# clvHd_EMG.net
KiCad netlist of a schematic drawn in EAGLE
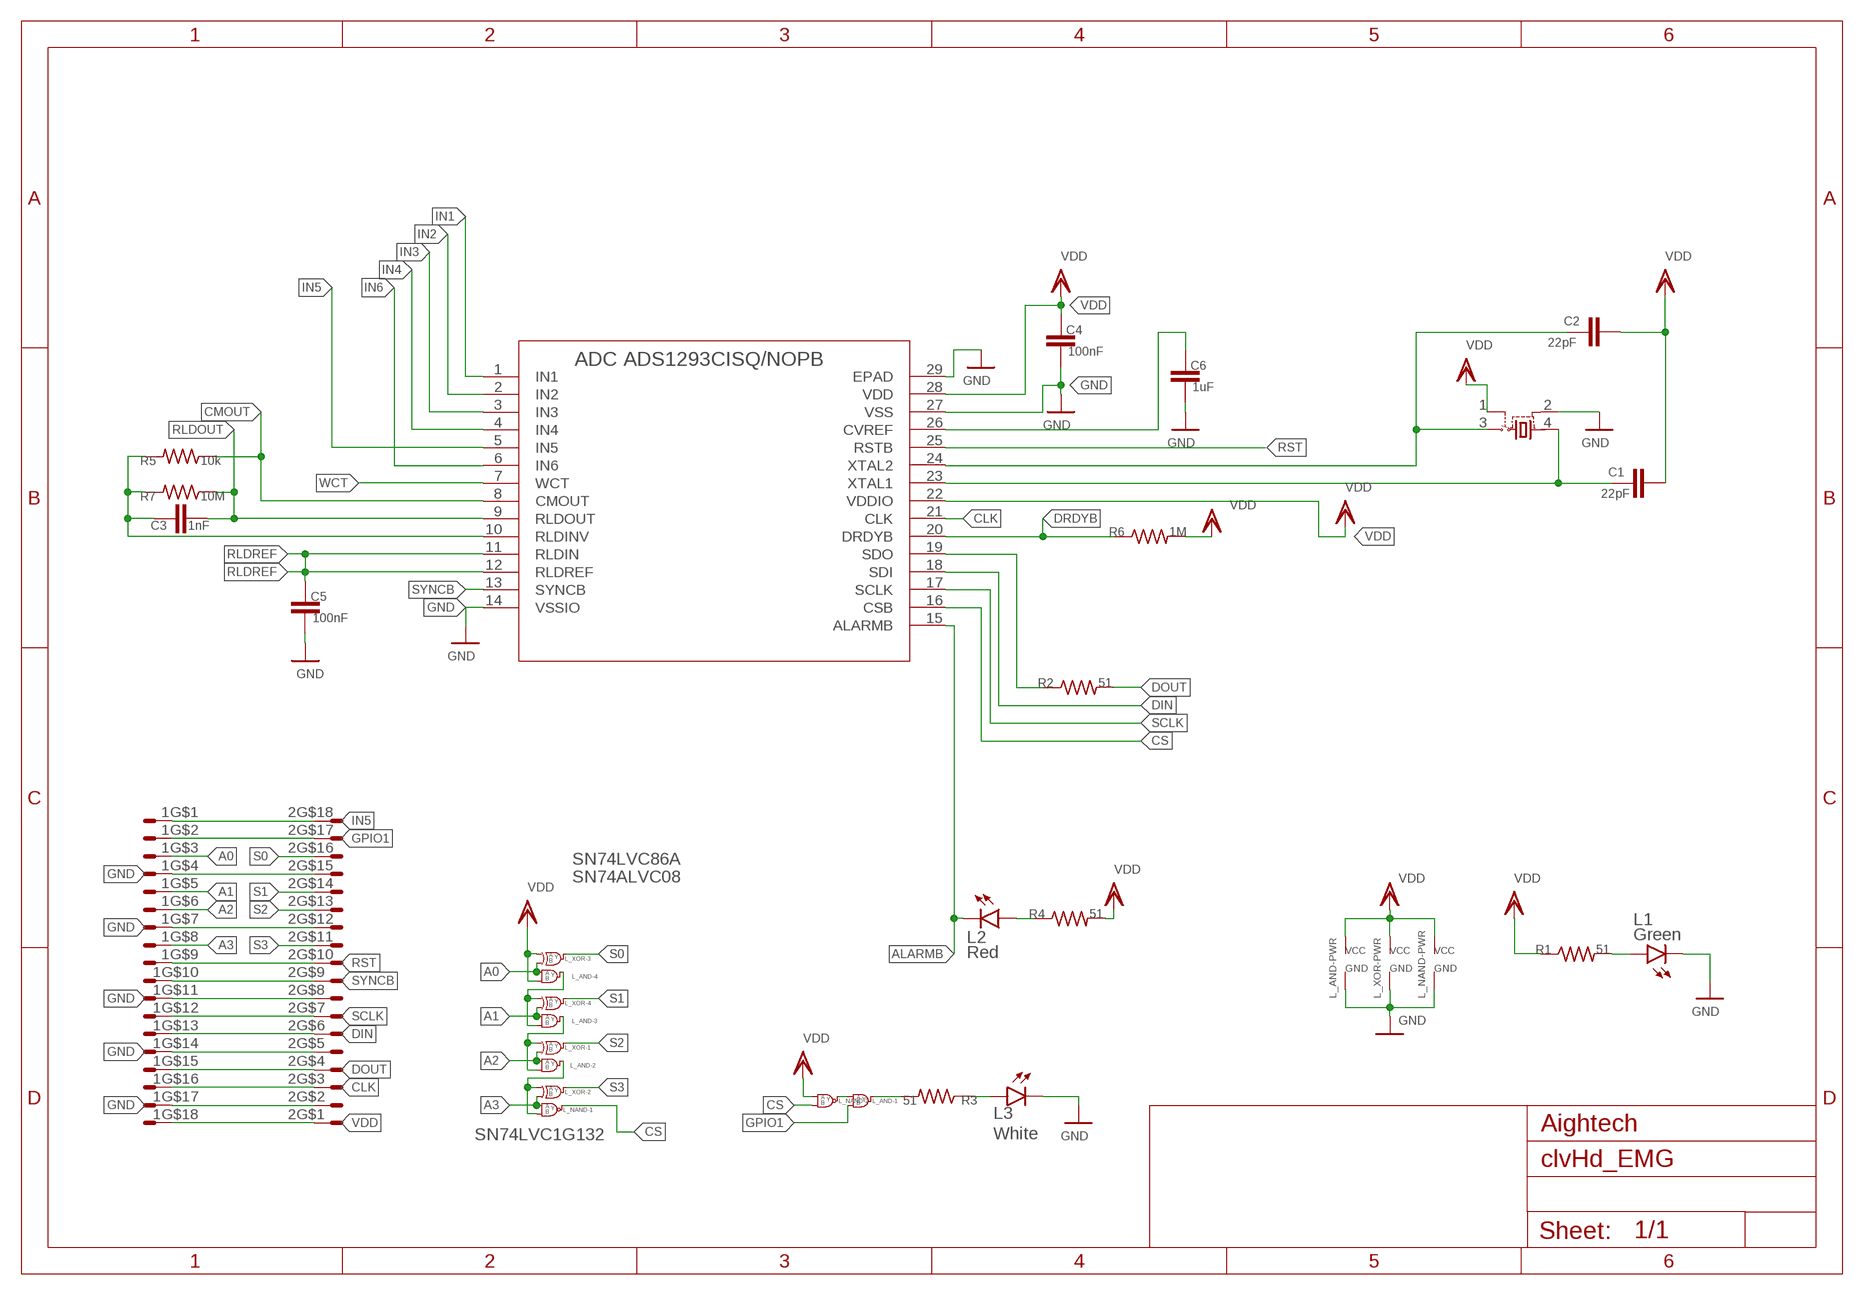
[diagram p0: schematic, sheet 1]

(export (version "E")
  (design (tool "Eeschema 10.0.6"))
  (components
    (comp (ref "1")
      (value "X05C2018TZ")
      (footprint "eagle-import:X05C2018TZ")
      (libsource (lib "eagle-import") (part "X05C2018TZ"))
    )
    (comp (ref "2")
      (value "X05C2018TZ")
      (footprint "eagle-import:X05C2018TZ")
      (libsource (lib "eagle-import") (part "X05C2018TZ"))
    )
    (comp (ref "ADC")
      (value "ADS1293CISQ/NOPB")
      (footprint "eagle-import:RSG28_3P6X3P6_TEX")
      (libsource (lib "eagle-import") (part "ADS1293CISQ/NOPB"))
    )
    (comp (ref "C1")
      (value "22pF")
      (footprint "eagle-import:C0402")
      (libsource (lib "eagle-import") (part "C-EUC0402"))
    )
    (comp (ref "C2")
      (value "22pF")
      (footprint "eagle-import:C0402")
      (libsource (lib "eagle-import") (part "C-EUC0402"))
    )
    (comp (ref "C3")
      (value "1nF")
      (footprint "eagle-import:C0402")
      (libsource (lib "eagle-import") (part "C-EUC0402"))
    )
    (comp (ref "C4")
      (value "100nF")
      (footprint "eagle-import:C0402")
      (libsource (lib "eagle-import") (part "C-EUC0402"))
    )
    (comp (ref "C5")
      (value "100nF")
      (footprint "eagle-import:C0402")
      (libsource (lib "eagle-import") (part "C-EUC0402"))
    )
    (comp (ref "C6")
      (value "1uF")
      (footprint "eagle-import:C0402")
      (libsource (lib "eagle-import") (part "C-EUC0402"))
    )
    (comp (ref "L1")
      (value "Green")
      (footprint "eagle-import:CHIP-LED0603")
      (libsource (lib "eagle-import") (part "LEDCHIP-LED0603"))
    )
    (comp (ref "L2")
      (value "Red")
      (footprint "eagle-import:CHIP-LED0603")
      (libsource (lib "eagle-import") (part "LEDCHIP-LED0603"))
    )
    (comp (ref "L3")
      (value "White")
      (footprint "eagle-import:CHIP-LED0603")
      (libsource (lib "eagle-import") (part "LEDCHIP-LED0603"))
    )
    (comp (ref "L_AND")
      (value "SN74ALVC08")
      (footprint "eagle-import:VQFN-14-CUSTOM")
      (libsource (lib "eagle-import") (part "SN74ALVC08RGY-LARGE"))
    )
    (comp (ref "L_NAND")
      (value "SN74AUP2G00")
      (footprint "eagle-import:VSSOP")
      (libsource (lib "eagle-import") (part "SN74AUP2G00DCU"))
    )
    (comp (ref "L_XOR")
      (value "SN74LVC86")
      (footprint "eagle-import:VQFN-14-CUSTOM")
      (libsource (lib "eagle-import") (part "SN74LVC86ARGY-LARGE"))
    )
    (comp (ref "R1")
      (value "51")
      (footprint "eagle-import:R0402")
      (libsource (lib "eagle-import") (part "rcl_334_R-US_R0402"))
    )
    (comp (ref "R2")
      (value "51")
      (footprint "eagle-import:R0402")
      (libsource (lib "eagle-import") (part "rcl_334_R-US_R0402"))
    )
    (comp (ref "R3")
      (value "51")
      (footprint "eagle-import:R0402")
      (libsource (lib "eagle-import") (part "rcl_334_R-US_R0402"))
    )
    (comp (ref "R4")
      (value "51")
      (footprint "eagle-import:R0402")
      (libsource (lib "eagle-import") (part "rcl_334_R-US_R0402"))
    )
    (comp (ref "R5")
      (value "10k")
      (footprint "eagle-import:R0402")
      (libsource (lib "eagle-import") (part "rcl_334_R-US_R0402"))
    )
    (comp (ref "R6")
      (value "1M")
      (footprint "eagle-import:R0402")
      (libsource (lib "eagle-import") (part "R-US_R0402"))
    )
    (comp (ref "R7")
      (value "10M")
      (footprint "eagle-import:R0402")
      (libsource (lib "eagle-import") (part "rcl_334_R-US_R0402"))
    )
    (comp (ref "TAL")
      (value "C387328")
      (footprint "eagle-import:SMD-3225_4P")
      (libsource (lib "eagle-import") (part "C387328"))
    )
  )
  (nets
    (net (code "1") (name "A0") (class "Default")
      (node (ref "1") (pin "3") (pinfunction "MS_3") (pintype "passive"))
      (node (ref "L_AND") (pin "12") (pinfunction "A_12") (pintype "input"))
      (node (ref "L_XOR") (pin "10") (pinfunction "B_10") (pintype "input"))
    )
    (net (code "2") (name "A1") (class "Default")
      (node (ref "1") (pin "5") (pinfunction "MS_5") (pintype "passive"))
      (node (ref "L_AND") (pin "9") (pinfunction "A_9") (pintype "input"))
      (node (ref "L_XOR") (pin "13") (pinfunction "B_13") (pintype "input"))
    )
    (net (code "3") (name "A2") (class "Default")
      (node (ref "1") (pin "6") (pinfunction "MS_6") (pintype "passive"))
      (node (ref "L_AND") (pin "4") (pinfunction "A_4") (pintype "input"))
      (node (ref "L_XOR") (pin "2") (pinfunction "B_2") (pintype "input"))
    )
    (net (code "4") (name "A3") (class "Default")
      (node (ref "1") (pin "8") (pinfunction "MS_8") (pintype "passive"))
      (node (ref "L_NAND") (pin "1") (pinfunction "A_1") (pintype "input"))
      (node (ref "L_XOR") (pin "5") (pinfunction "B_5") (pintype "input"))
    )
    (net (code "5") (name "ALARMB") (class "Default")
      (node (ref "ADC") (pin "15") (pinfunction "ALARMB_15") (pintype "output"))
      (node (ref "L2") (pin "C") (pinfunction "C_C") (pintype "passive"))
    )
    (net (code "6") (name "CLK") (class "Default")
      (node (ref "1") (pin "16") (pinfunction "MS_16") (pintype "passive"))
      (node (ref "2") (pin "3") (pinfunction "MS_3") (pintype "passive"))
      (node (ref "ADC") (pin "21") (pinfunction "CLK_21") (pintype "bidirectional"))
    )
    (net (code "7") (name "CMOUT") (class "Default")
      (node (ref "ADC") (pin "8") (pinfunction "CMOUT_8") (pintype "output"))
      (node (ref "R5") (pin "1") (pinfunction "1_1") (pintype "passive"))
    )
    (net (code "8") (name "CS") (class "Default")
      (node (ref "ADC") (pin "16") (pinfunction "CSB_16") (pintype "input"))
      (node (ref "L_NAND") (pin "6") (pinfunction "B_6") (pintype "input"))
      (node (ref "L_NAND") (pin "7") (pinfunction "Y_7") (pintype "output"))
    )
    (net (code "9") (name "DIN") (class "Default")
      (node (ref "1") (pin "13") (pinfunction "MS_13") (pintype "passive"))
      (node (ref "2") (pin "6") (pinfunction "MS_6") (pintype "passive"))
      (node (ref "ADC") (pin "18") (pinfunction "SDI_18") (pintype "input"))
    )
    (net (code "10") (name "DOUT") (class "Default")
      (node (ref "1") (pin "15") (pinfunction "MS_15") (pintype "passive"))
      (node (ref "2") (pin "4") (pinfunction "MS_4") (pintype "passive"))
      (node (ref "R2") (pin "2") (pinfunction "2_2") (pintype "passive"))
    )
    (net (code "11") (name "DRDYB") (class "Default")
      (node (ref "ADC") (pin "20") (pinfunction "DRDYB_20") (pintype "output"))
      (node (ref "R6") (pin "1") (pinfunction "1_1") (pintype "passive"))
    )
    (net (code "12") (name "GND") (class "Default")
      (node (ref "1") (pin "11") (pinfunction "MS_11") (pintype "passive"))
      (node (ref "1") (pin "14") (pinfunction "MS_14") (pintype "passive"))
      (node (ref "1") (pin "17") (pinfunction "MS_17") (pintype "passive"))
      (node (ref "1") (pin "4") (pinfunction "MS_4") (pintype "passive"))
      (node (ref "1") (pin "7") (pinfunction "MS_7") (pintype "passive"))
      (node (ref "2") (pin "12") (pinfunction "MS_12") (pintype "passive"))
      (node (ref "2") (pin "15") (pinfunction "MS_15") (pintype "passive"))
      (node (ref "2") (pin "2") (pinfunction "MS_2") (pintype "passive"))
      (node (ref "2") (pin "5") (pinfunction "MS_5") (pintype "passive"))
      (node (ref "2") (pin "8") (pinfunction "MS_8") (pintype "passive"))
      (node (ref "ADC") (pin "14") (pinfunction "VSSIO_14") (pintype "power_in"))
      (node (ref "ADC") (pin "27") (pinfunction "VSS_27") (pintype "power_in"))
      (node (ref "ADC") (pin "29") (pinfunction "EPAD_29") (pintype "passive"))
      (node (ref "C4") (pin "2") (pinfunction "2_2") (pintype "passive"))
      (node (ref "C5") (pin "2") (pinfunction "2_2") (pintype "passive"))
      (node (ref "C6") (pin "2") (pinfunction "2_2") (pintype "passive"))
      (node (ref "L1") (pin "C") (pinfunction "C_C") (pintype "passive"))
      (node (ref "L3") (pin "C") (pinfunction "C_C") (pintype "passive"))
      (node (ref "L_AND") (pin "15") (pinfunction "GND_15") (pintype "power_in"))
      (node (ref "L_AND") (pin "7") (pinfunction "GND_7") (pintype "power_in"))
      (node (ref "L_NAND") (pin "4") (pinfunction "GND_4") (pintype "power_in"))
      (node (ref "L_XOR") (pin "15") (pinfunction "GND_15") (pintype "power_in"))
      (node (ref "L_XOR") (pin "7") (pinfunction "GND_7") (pintype "power_in"))
      (node (ref "TAL") (pin "2") (pinfunction "GND_2") (pintype "power_in"))
    )
    (net (code "13") (name "GPIO1") (class "Default")
      (node (ref "1") (pin "2") (pinfunction "MS_2") (pintype "passive"))
      (node (ref "2") (pin "17") (pinfunction "MS_17") (pintype "passive"))
      (node (ref "L_AND") (pin "2") (pinfunction "B_2") (pintype "input"))
    )
    (net (code "14") (name "IN1") (class "Default")
      (node (ref "ADC") (pin "1") (pinfunction "IN1_1") (pintype "input"))
    )
    (net (code "15") (name "IN2") (class "Default")
      (node (ref "ADC") (pin "2") (pinfunction "IN2_2") (pintype "input"))
    )
    (net (code "16") (name "IN3") (class "Default")
      (node (ref "ADC") (pin "3") (pinfunction "IN3_3") (pintype "input"))
    )
    (net (code "17") (name "IN4") (class "Default")
      (node (ref "ADC") (pin "4") (pinfunction "IN4_4") (pintype "input"))
    )
    (net (code "18") (name "IN5") (class "Default")
      (node (ref "1") (pin "1") (pinfunction "MS_1") (pintype "passive"))
      (node (ref "2") (pin "18") (pinfunction "MS_18") (pintype "passive"))
      (node (ref "ADC") (pin "5") (pinfunction "IN5_5") (pintype "input"))
    )
    (net (code "19") (name "IN6") (class "Default")
      (node (ref "ADC") (pin "6") (pinfunction "IN6_6") (pintype "input"))
    )
    (net (code "20") (name "Net-(ADC-CVREF)") (class "Default")
      (node (ref "ADC") (pin "26") (pinfunction "CVREF_26") (pintype "bidirectional"))
      (node (ref "C6") (pin "1") (pinfunction "1_1") (pintype "passive"))
    )
    (net (code "21") (name "Net-(ADC-RLDINV)") (class "Default")
      (node (ref "ADC") (pin "10") (pinfunction "RLDINV_10") (pintype "input"))
      (node (ref "C3") (pin "1") (pinfunction "1_1") (pintype "passive"))
      (node (ref "R5") (pin "2") (pinfunction "2_2") (pintype "passive"))
      (node (ref "R7") (pin "2") (pinfunction "2_2") (pintype "passive"))
    )
    (net (code "22") (name "Net-(ADC-SDO)") (class "Default")
      (node (ref "ADC") (pin "19") (pinfunction "SDO_19") (pintype "output"))
      (node (ref "R2") (pin "1") (pinfunction "1_1") (pintype "passive"))
    )
    (net (code "23") (name "Net-(ADC-XTAL1)") (class "Default")
      (node (ref "ADC") (pin "23") (pinfunction "XTAL1_23") (pintype "input"))
      (node (ref "C1") (pin "2") (pinfunction "2_2") (pintype "passive"))
      (node (ref "TAL") (pin "4") (pinfunction "VDD_4") (pintype "power_in"))
    )
    (net (code "24") (name "Net-(ADC-XTAL2)") (class "Default")
      (node (ref "ADC") (pin "24") (pinfunction "XTAL2_24") (pintype "input"))
      (node (ref "C2") (pin "2") (pinfunction "2_2") (pintype "passive"))
      (node (ref "TAL") (pin "3") (pinfunction "OUT_3") (pintype "output"))
    )
    (net (code "25") (name "Net-(L1-PadA)") (class "Default")
      (node (ref "L1") (pin "A") (pinfunction "A_A") (pintype "passive"))
      (node (ref "R1") (pin "2") (pinfunction "2_2") (pintype "passive"))
    )
    (net (code "26") (name "Net-(L2-PadA)") (class "Default")
      (node (ref "L2") (pin "A") (pinfunction "A_A") (pintype "passive"))
      (node (ref "R4") (pin "1") (pinfunction "1_1") (pintype "passive"))
    )
    (net (code "27") (name "Net-(L3-PadA)") (class "Default")
      (node (ref "L3") (pin "A") (pinfunction "A_A") (pintype "passive"))
      (node (ref "R3") (pin "1") (pinfunction "1_1") (pintype "passive"))
    )
    (net (code "28") (name "Net-(L_ANDA-A)") (class "Default")
      (node (ref "L_AND") (pin "1") (pinfunction "A_1") (pintype "input"))
      (node (ref "L_NAND") (pin "3") (pinfunction "Y_3") (pintype "output"))
    )
    (net (code "29") (name "Net-(L_ANDA-Y)") (class "Default")
      (node (ref "L_AND") (pin "3") (pinfunction "Y_3") (pintype "output"))
      (node (ref "R3") (pin "2") (pinfunction "2_2") (pintype "passive"))
    )
    (net (code "30") (name "Net-(L_ANDB-B)") (class "Default")
      (node (ref "L_AND") (pin "5") (pinfunction "B_5") (pintype "input"))
      (node (ref "L_AND") (pin "8") (pinfunction "Y_8") (pintype "output"))
      (node (ref "L_XOR") (pin "1") (pinfunction "A_1") (pintype "input"))
    )
    (net (code "31") (name "Net-(L_ANDB-Y)") (class "Default")
      (node (ref "L_AND") (pin "6") (pinfunction "Y_6") (pintype "output"))
      (node (ref "L_NAND") (pin "2") (pinfunction "B_2") (pintype "input"))
      (node (ref "L_XOR") (pin "4") (pinfunction "A_4") (pintype "input"))
    )
    (net (code "32") (name "Net-(L_ANDC-B)") (class "Default")
      (node (ref "L_AND") (pin "10") (pinfunction "B_10") (pintype "input"))
      (node (ref "L_AND") (pin "11") (pinfunction "Y_11") (pintype "output"))
      (node (ref "L_XOR") (pin "12") (pinfunction "A_12") (pintype "input"))
    )
    (net (code "33") (name "RLDOUT") (class "Default")
      (node (ref "ADC") (pin "9") (pinfunction "RLDOUT_9") (pintype "output"))
      (node (ref "C3") (pin "2") (pinfunction "2_2") (pintype "passive"))
      (node (ref "R7") (pin "1") (pinfunction "1_1") (pintype "passive"))
    )
    (net (code "34") (name "RLDREF") (class "Default")
      (node (ref "ADC") (pin "11") (pinfunction "RLDIN_11") (pintype "bidirectional"))
      (node (ref "ADC") (pin "12") (pinfunction "RLDREF_12") (pintype "output"))
      (node (ref "C5") (pin "1") (pinfunction "1_1") (pintype "passive"))
    )
    (net (code "35") (name "RST") (class "Default")
      (node (ref "1") (pin "9") (pinfunction "MS_9") (pintype "passive"))
      (node (ref "2") (pin "10") (pinfunction "MS_10") (pintype "passive"))
      (node (ref "ADC") (pin "25") (pinfunction "RSTB_25") (pintype "input"))
    )
    (net (code "36") (name "S0") (class "Default")
      (node (ref "2") (pin "16") (pinfunction "MS_16") (pintype "passive"))
      (node (ref "L_XOR") (pin "8") (pinfunction "Y_8") (pintype "output"))
    )
    (net (code "37") (name "S1") (class "Default")
      (node (ref "2") (pin "14") (pinfunction "MS_14") (pintype "passive"))
      (node (ref "L_XOR") (pin "11") (pinfunction "Y_11") (pintype "output"))
    )
    (net (code "38") (name "S2") (class "Default")
      (node (ref "2") (pin "13") (pinfunction "MS_13") (pintype "passive"))
      (node (ref "L_XOR") (pin "3") (pinfunction "Y_3") (pintype "output"))
    )
    (net (code "39") (name "S3") (class "Default")
      (node (ref "2") (pin "11") (pinfunction "MS_11") (pintype "passive"))
      (node (ref "L_XOR") (pin "6") (pinfunction "Y_6") (pintype "output"))
    )
    (net (code "40") (name "SCLK") (class "Default")
      (node (ref "1") (pin "12") (pinfunction "MS_12") (pintype "passive"))
      (node (ref "2") (pin "7") (pinfunction "MS_7") (pintype "passive"))
      (node (ref "ADC") (pin "17") (pinfunction "SCLK_17") (pintype "input"))
    )
    (net (code "41") (name "SYNCB") (class "Default")
      (node (ref "1") (pin "10") (pinfunction "MS_10") (pintype "passive"))
      (node (ref "2") (pin "9") (pinfunction "MS_9") (pintype "passive"))
      (node (ref "ADC") (pin "13") (pinfunction "SYNCB_13") (pintype "bidirectional"))
    )
    (net (code "42") (name "VDD") (class "Default")
      (node (ref "1") (pin "18") (pinfunction "MS_18") (pintype "passive"))
      (node (ref "2") (pin "1") (pinfunction "MS_1") (pintype "passive"))
      (node (ref "ADC") (pin "22") (pinfunction "VDDIO_22") (pintype "power_in"))
      (node (ref "ADC") (pin "28") (pinfunction "VDD_28") (pintype "power_in"))
      (node (ref "C1") (pin "1") (pinfunction "1_1") (pintype "passive"))
      (node (ref "C2") (pin "1") (pinfunction "1_1") (pintype "passive"))
      (node (ref "C4") (pin "1") (pinfunction "1_1") (pintype "passive"))
      (node (ref "L_AND") (pin "13") (pinfunction "B_13") (pintype "input"))
      (node (ref "L_AND") (pin "14") (pinfunction "VCC_14") (pintype "power_in"))
      (node (ref "L_NAND") (pin "5") (pinfunction "A_5") (pintype "input"))
      (node (ref "L_NAND") (pin "8") (pinfunction "VCC_8") (pintype "power_in"))
      (node (ref "L_XOR") (pin "14") (pinfunction "VCC_14") (pintype "power_in"))
      (node (ref "L_XOR") (pin "9") (pinfunction "A_9") (pintype "input"))
      (node (ref "R1") (pin "1") (pinfunction "1_1") (pintype "passive"))
      (node (ref "R4") (pin "2") (pinfunction "2_2") (pintype "passive"))
      (node (ref "R6") (pin "2") (pinfunction "2_2") (pintype "passive"))
      (node (ref "TAL") (pin "1") (pinfunction "TRI_1") (pintype "input"))
    )
    (net (code "43") (name "WCT") (class "Default")
      (node (ref "ADC") (pin "7") (pinfunction "WCT_7") (pintype "output"))
    )
  )
)
